# SCH_ADC-To-Multiple-Switches.net
KiCad netlist of a schematic drawn in EasyEDA
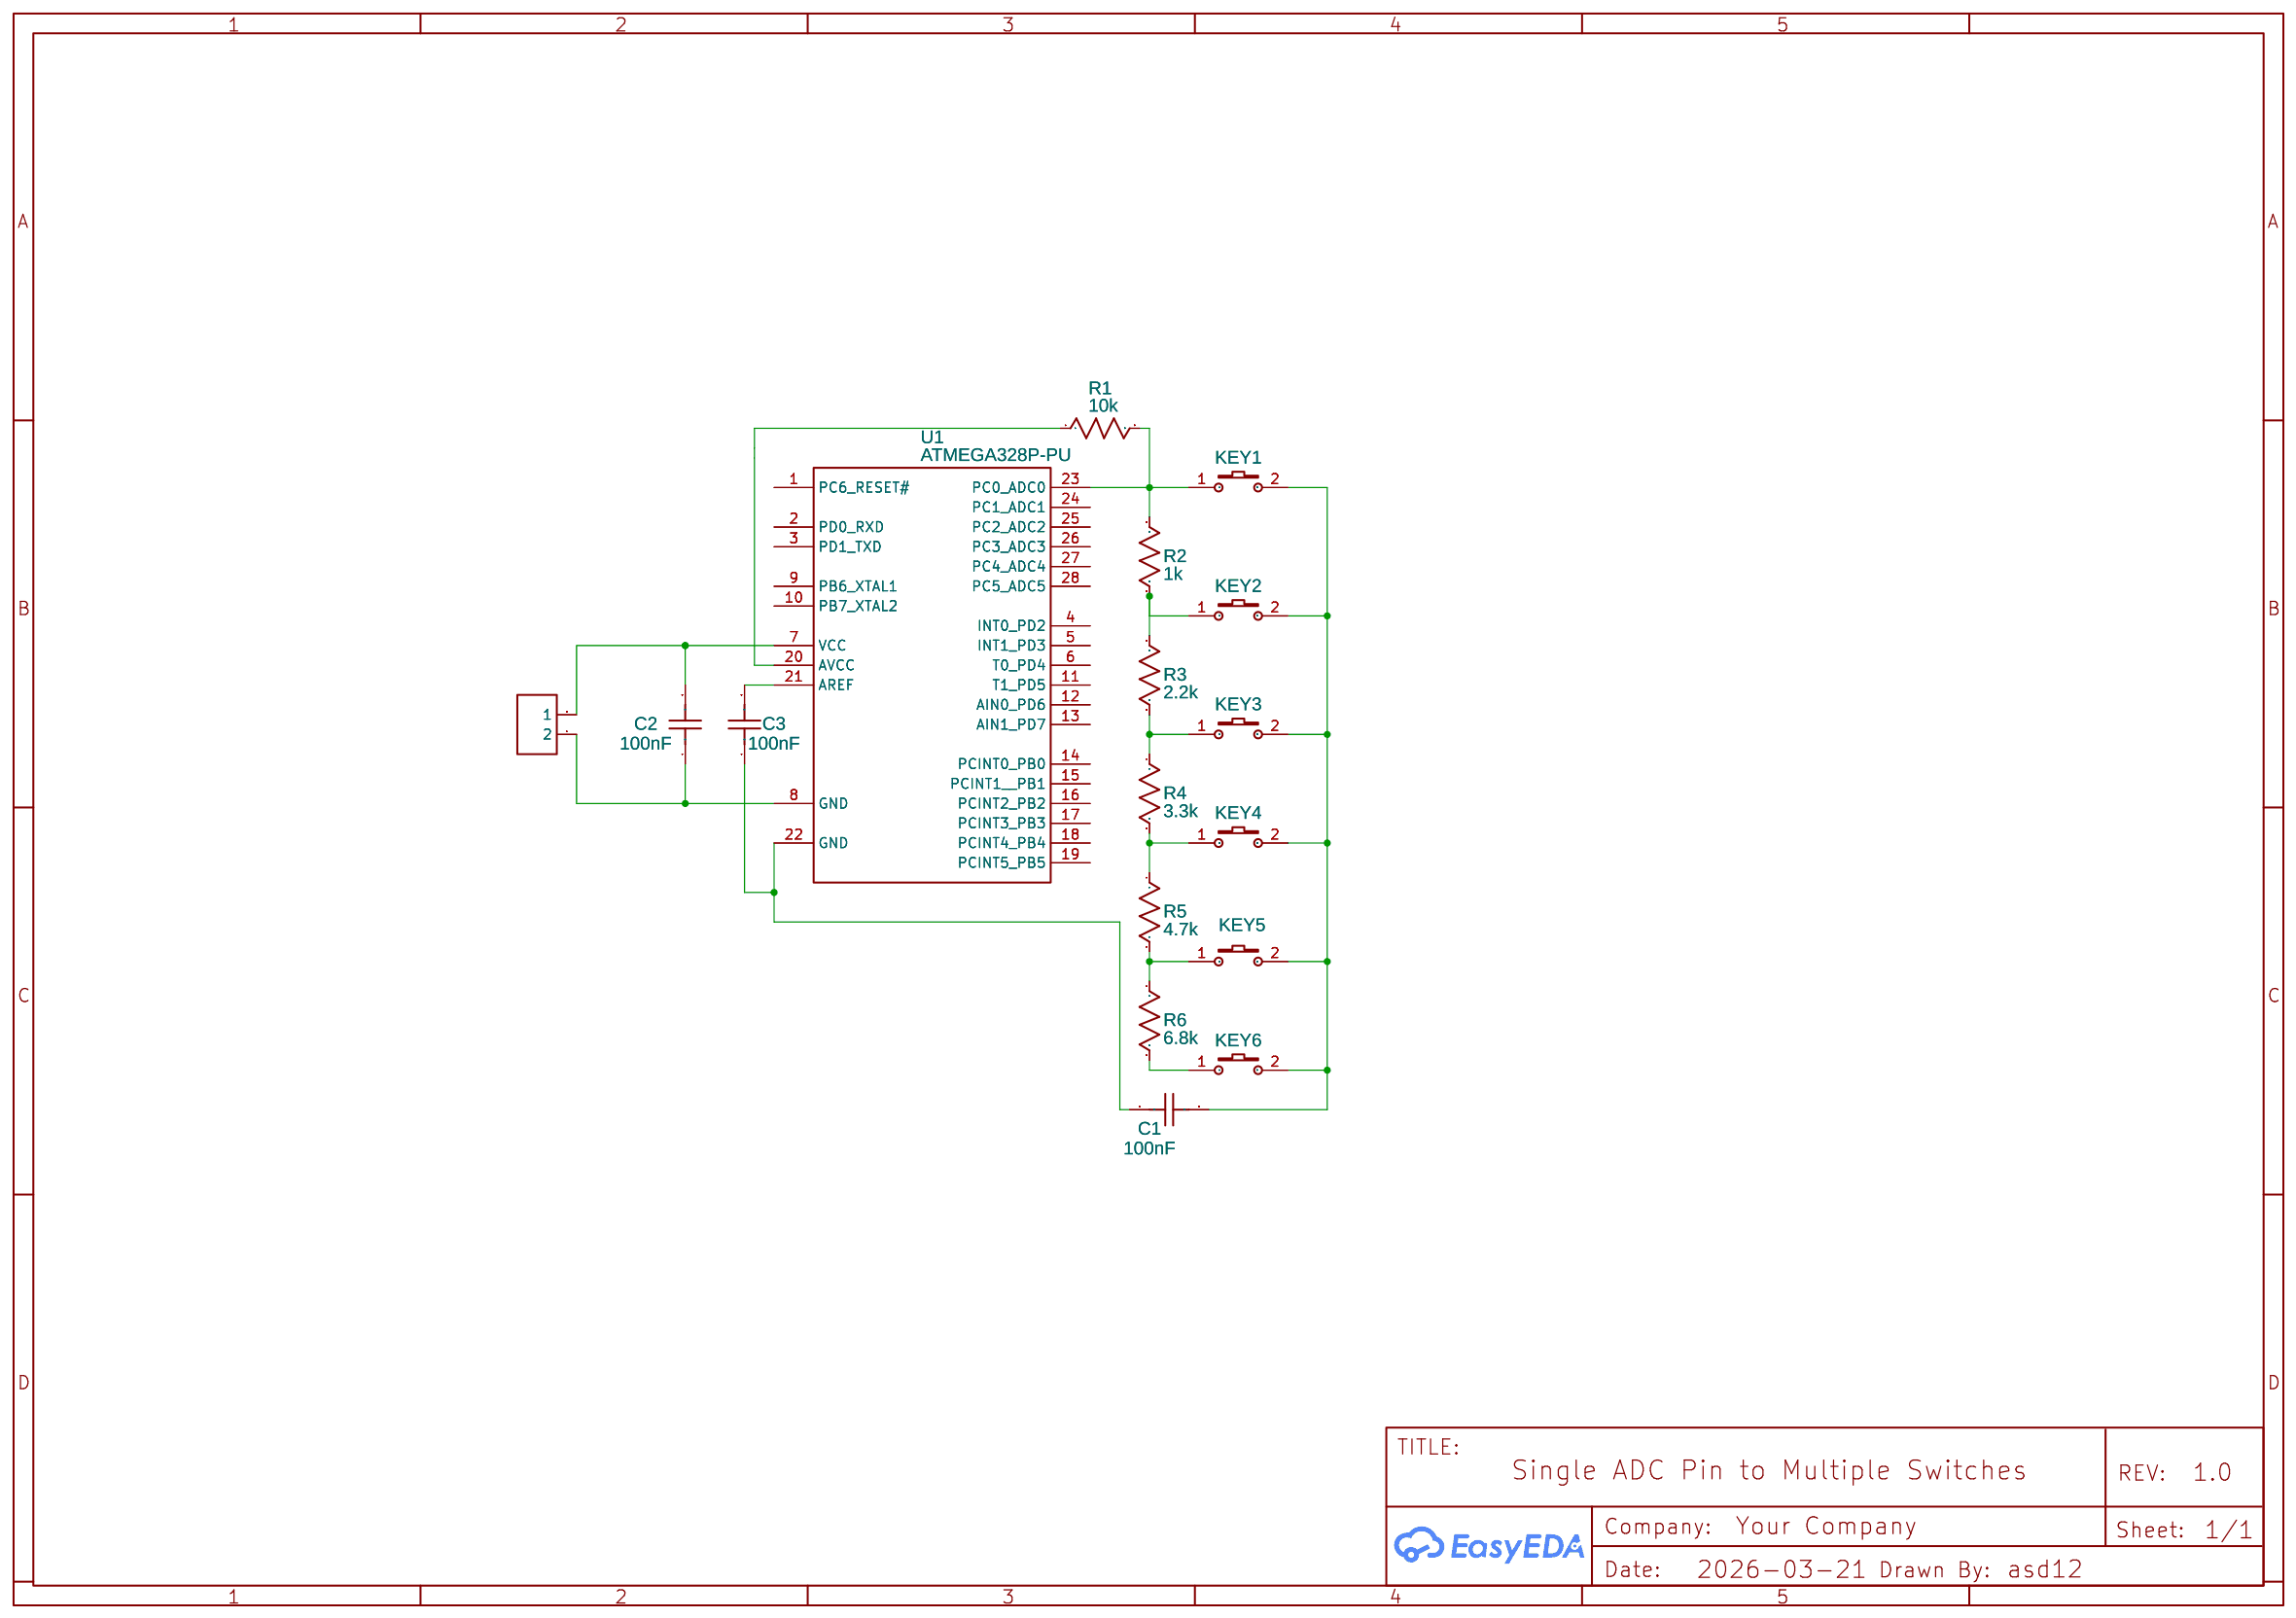
[diagram p0: schematic sheet]

(export (version "E")
  (design (tool "Eeschema 10.0.6"))
  (components
    (comp (ref "C1") (value "100nF") (libsource (lib "") (part "C_0603_US_1")))
    (comp (ref "C2") (value "100nF") (libsource (lib "") (part "C_0603_US")))
    (comp (ref "C3") (value "100nF") (libsource (lib "") (part "C_0603_US")))
    (comp (ref "KEY1")
      (value "K2-3.6×6.1_SMD")
      (fields (field (name "Manufacturer Part") "K2-1107ST-A4SW-06"))
      (libsource (lib "") (part "K2-3.6×6.1_SMD"))
    )
    (comp (ref "KEY2")
      (value "K2-3.6×6.1_SMD")
      (fields (field (name "Manufacturer Part") "K2-1107ST-A4SW-06"))
      (libsource (lib "") (part "K2-3.6×6.1_SMD"))
    )
    (comp (ref "KEY3")
      (value "K2-3.6×6.1_SMD")
      (fields (field (name "Manufacturer Part") "K2-1107ST-A4SW-06"))
      (libsource (lib "") (part "K2-3.6×6.1_SMD"))
    )
    (comp (ref "KEY4")
      (value "K2-3.6×6.1_SMD")
      (fields (field (name "Manufacturer Part") "K2-1107ST-A4SW-06"))
      (libsource (lib "") (part "K2-3.6×6.1_SMD"))
    )
    (comp (ref "KEY5")
      (value "K2-3.6×6.1_SMD")
      (fields (field (name "Manufacturer Part") "K2-1107ST-A4SW-06"))
      (libsource (lib "") (part "K2-3.6×6.1_SMD"))
    )
    (comp (ref "KEY6")
      (value "K2-3.6×6.1_SMD")
      (fields (field (name "Manufacturer Part") "K2-1107ST-A4SW-06"))
      (libsource (lib "") (part "K2-3.6×6.1_SMD"))
    )
    (comp (ref "P1") (value "CONN-TH_2P-P5.00") (libsource (lib "") (part "CONN-TH_2P-P5.00")))
    (comp (ref "R1") (value "10k") (libsource (lib "") (part "R_0603_US_1")))
    (comp (ref "R2") (value "1k") (libsource (lib "") (part "R_0603_US")))
    (comp (ref "R3") (value "2.2k") (libsource (lib "") (part "R_0603_US")))
    (comp (ref "R4") (value "3.3k") (libsource (lib "") (part "R_0603_US")))
    (comp (ref "R5") (value "4.7k") (libsource (lib "") (part "R_0603_US")))
    (comp (ref "R6") (value "6.8k") (libsource (lib "") (part "R_0603_US")))
    (comp (ref "U1")
      (value "ATMEGA328P-PU")
      (fields (field (name "Manufacturer") "MICROCHIP(美国微芯)"))
      (libsource (lib "") (part "ATMEGA328P-PU"))
    )
  )
  (nets
    (net (code "1") (name "Net-(C1-Pad1)") (class "Default")
      (node (ref "C1") (pin "1") (pinfunction "1_1") (pintype "unspecified"))
      (node (ref "C3") (pin "1") (pinfunction "1_1") (pintype "unspecified"))
      (node (ref "U1") (pin "22") (pinfunction "GND_22") (pintype "passive"))
    )
    (net (code "2") (name "Net-(C1-Pad2)") (class "Default")
      (node (ref "C1") (pin "2") (pinfunction "2_2") (pintype "unspecified"))
      (node (ref "KEY1") (pin "2") (pinfunction "2_2") (pintype "unspecified"))
      (node (ref "KEY2") (pin "2") (pinfunction "2_2") (pintype "unspecified"))
      (node (ref "KEY3") (pin "2") (pinfunction "2_2") (pintype "unspecified"))
      (node (ref "KEY4") (pin "2") (pinfunction "2_2") (pintype "unspecified"))
      (node (ref "KEY5") (pin "2") (pinfunction "2_2") (pintype "unspecified"))
      (node (ref "KEY6") (pin "2") (pinfunction "2_2") (pintype "unspecified"))
    )
    (net (code "3") (name "Net-(KEY2-Pad1)") (class "Default")
      (node (ref "KEY2") (pin "1") (pinfunction "1_1") (pintype "unspecified"))
      (node (ref "R2") (pin "2") (pinfunction "2_2") (pintype "unspecified"))
      (node (ref "R3") (pin "1") (pinfunction "1_1") (pintype "unspecified"))
    )
    (net (code "4") (name "Net-(KEY3-Pad1)") (class "Default")
      (node (ref "KEY3") (pin "1") (pinfunction "1_1") (pintype "unspecified"))
      (node (ref "R3") (pin "2") (pinfunction "2_2") (pintype "unspecified"))
      (node (ref "R4") (pin "1") (pinfunction "1_1") (pintype "unspecified"))
    )
    (net (code "5") (name "Net-(KEY4-Pad1)") (class "Default")
      (node (ref "KEY4") (pin "1") (pinfunction "1_1") (pintype "unspecified"))
      (node (ref "R4") (pin "2") (pinfunction "2_2") (pintype "unspecified"))
      (node (ref "R5") (pin "1") (pinfunction "1_1") (pintype "unspecified"))
    )
    (net (code "6") (name "Net-(KEY5-Pad1)") (class "Default")
      (node (ref "KEY5") (pin "1") (pinfunction "1_1") (pintype "unspecified"))
      (node (ref "R5") (pin "2") (pinfunction "2_2") (pintype "unspecified"))
      (node (ref "R6") (pin "1") (pinfunction "1_1") (pintype "unspecified"))
    )
    (net (code "7") (name "Net-(KEY6-Pad1)") (class "Default")
      (node (ref "KEY6") (pin "1") (pinfunction "1_1") (pintype "unspecified"))
      (node (ref "R6") (pin "2") (pinfunction "2_2") (pintype "unspecified"))
    )
    (net (code "8") (name "Net-(P1-1)") (class "Default")
      (node (ref "C2") (pin "2") (pinfunction "2_2") (pintype "unspecified"))
      (node (ref "P1") (pin "2") (pinfunction "1_2") (pintype "unspecified"))
      (node (ref "U1") (pin "7") (pinfunction "VCC_7") (pintype "passive"))
    )
    (net (code "9") (name "Net-(P1-2)") (class "Default")
      (node (ref "C2") (pin "1") (pinfunction "1_1") (pintype "unspecified"))
      (node (ref "P1") (pin "1") (pinfunction "2_1") (pintype "unspecified"))
      (node (ref "U1") (pin "8") (pinfunction "GND_8") (pintype "passive"))
    )
    (net (code "10") (name "Net-(U1-AREF)") (class "Default")
      (node (ref "C3") (pin "2") (pinfunction "2_2") (pintype "unspecified"))
      (node (ref "U1") (pin "21") (pinfunction "AREF_21") (pintype "passive"))
    )
    (net (code "11") (name "Net-(U1-AVCC)") (class "Default")
      (node (ref "R1") (pin "1") (pinfunction "1_1") (pintype "unspecified"))
      (node (ref "U1") (pin "20") (pinfunction "AVCC_20") (pintype "passive"))
    )
    (net (code "12") (name "Net-(U1-PC0_ADC0)") (class "Default")
      (node (ref "KEY1") (pin "1") (pinfunction "1_1") (pintype "unspecified"))
      (node (ref "R1") (pin "2") (pinfunction "2_2") (pintype "unspecified"))
      (node (ref "R2") (pin "1") (pinfunction "1_1") (pintype "unspecified"))
      (node (ref "U1") (pin "23") (pinfunction "PC0_ADC0_23") (pintype "bidirectional"))
    )
    (net (code "13") (name "unconnected-(U1-AIN0_PD6-Pad12)") (class "Default")
      (node (ref "U1") (pin "12") (pinfunction "AIN0_PD6_12") (pintype "bidirectional"))
    )
    (net (code "14") (name "unconnected-(U1-AIN1_PD7-Pad13)") (class "Default")
      (node (ref "U1") (pin "13") (pinfunction "AIN1_PD7_13") (pintype "bidirectional"))
    )
    (net (code "15") (name "unconnected-(U1-INT0_PD2-Pad4)") (class "Default")
      (node (ref "U1") (pin "4") (pinfunction "INT0_PD2_4") (pintype "bidirectional"))
    )
    (net (code "16") (name "unconnected-(U1-INT1_PD3-Pad5)") (class "Default")
      (node (ref "U1") (pin "5") (pinfunction "INT1_PD3_5") (pintype "bidirectional"))
    )
    (net (code "17") (name "unconnected-(U1-PB6_XTAL1-Pad9)") (class "Default")
      (node (ref "U1") (pin "9") (pinfunction "PB6_XTAL1_9") (pintype "bidirectional"))
    )
    (net (code "18") (name "unconnected-(U1-PB7_XTAL2-Pad10)") (class "Default")
      (node (ref "U1") (pin "10") (pinfunction "PB7_XTAL2_10") (pintype "bidirectional"))
    )
    (net (code "19") (name "unconnected-(U1-PC1_ADC1-Pad24)") (class "Default")
      (node (ref "U1") (pin "24") (pinfunction "PC1_ADC1_24") (pintype "bidirectional"))
    )
    (net (code "20") (name "unconnected-(U1-PC2_ADC2-Pad25)") (class "Default")
      (node (ref "U1") (pin "25") (pinfunction "PC2_ADC2_25") (pintype "bidirectional"))
    )
    (net (code "21") (name "unconnected-(U1-PC3_ADC3-Pad26)") (class "Default")
      (node (ref "U1") (pin "26") (pinfunction "PC3_ADC3_26") (pintype "bidirectional"))
    )
    (net (code "22") (name "unconnected-(U1-PC4_ADC4-Pad27)") (class "Default")
      (node (ref "U1") (pin "27") (pinfunction "PC4_ADC4_27") (pintype "bidirectional"))
    )
    (net (code "23") (name "unconnected-(U1-PC5_ADC5-Pad28)") (class "Default")
      (node (ref "U1") (pin "28") (pinfunction "PC5_ADC5_28") (pintype "bidirectional"))
    )
    (net (code "24") (name "unconnected-(U1-PC6_RESET#-Pad1)") (class "Default")
      (node (ref "U1") (pin "1") (pinfunction "PC6_RESET#_1") (pintype "bidirectional"))
    )
    (net (code "25") (name "unconnected-(U1-PCINT0_PB0-Pad14)") (class "Default")
      (node (ref "U1") (pin "14") (pinfunction "PCINT0_PB0_14") (pintype "bidirectional"))
    )
    (net (code "26") (name "unconnected-(U1-PCINT1__PB1-Pad15)") (class "Default")
      (node (ref "U1") (pin "15") (pinfunction "PCINT1__PB1_15") (pintype "bidirectional"))
    )
    (net (code "27") (name "unconnected-(U1-PCINT2_PB2-Pad16)") (class "Default")
      (node (ref "U1") (pin "16") (pinfunction "PCINT2_PB2_16") (pintype "bidirectional"))
    )
    (net (code "28") (name "unconnected-(U1-PCINT3_PB3-Pad17)") (class "Default")
      (node (ref "U1") (pin "17") (pinfunction "PCINT3_PB3_17") (pintype "bidirectional"))
    )
    (net (code "29") (name "unconnected-(U1-PCINT4_PB4-Pad18)") (class "Default")
      (node (ref "U1") (pin "18") (pinfunction "PCINT4_PB4_18") (pintype "bidirectional"))
    )
    (net (code "30") (name "unconnected-(U1-PCINT5_PB5-Pad19)") (class "Default")
      (node (ref "U1") (pin "19") (pinfunction "PCINT5_PB5_19") (pintype "bidirectional"))
    )
    (net (code "31") (name "unconnected-(U1-PD0_RXD-Pad2)") (class "Default")
      (node (ref "U1") (pin "2") (pinfunction "PD0_RXD_2") (pintype "bidirectional"))
    )
    (net (code "32") (name "unconnected-(U1-PD1_TXD-Pad3)") (class "Default")
      (node (ref "U1") (pin "3") (pinfunction "PD1_TXD_3") (pintype "bidirectional"))
    )
    (net (code "33") (name "unconnected-(U1-T0_PD4-Pad6)") (class "Default")
      (node (ref "U1") (pin "6") (pinfunction "T0_PD4_6") (pintype "bidirectional"))
    )
    (net (code "34") (name "unconnected-(U1-T1_PD5-Pad11)") (class "Default")
      (node (ref "U1") (pin "11") (pinfunction "T1_PD5_11") (pintype "bidirectional"))
    )
  )
)
